# Low_MOS.net
KiCad netlist of a schematic drawn in Altium Designer
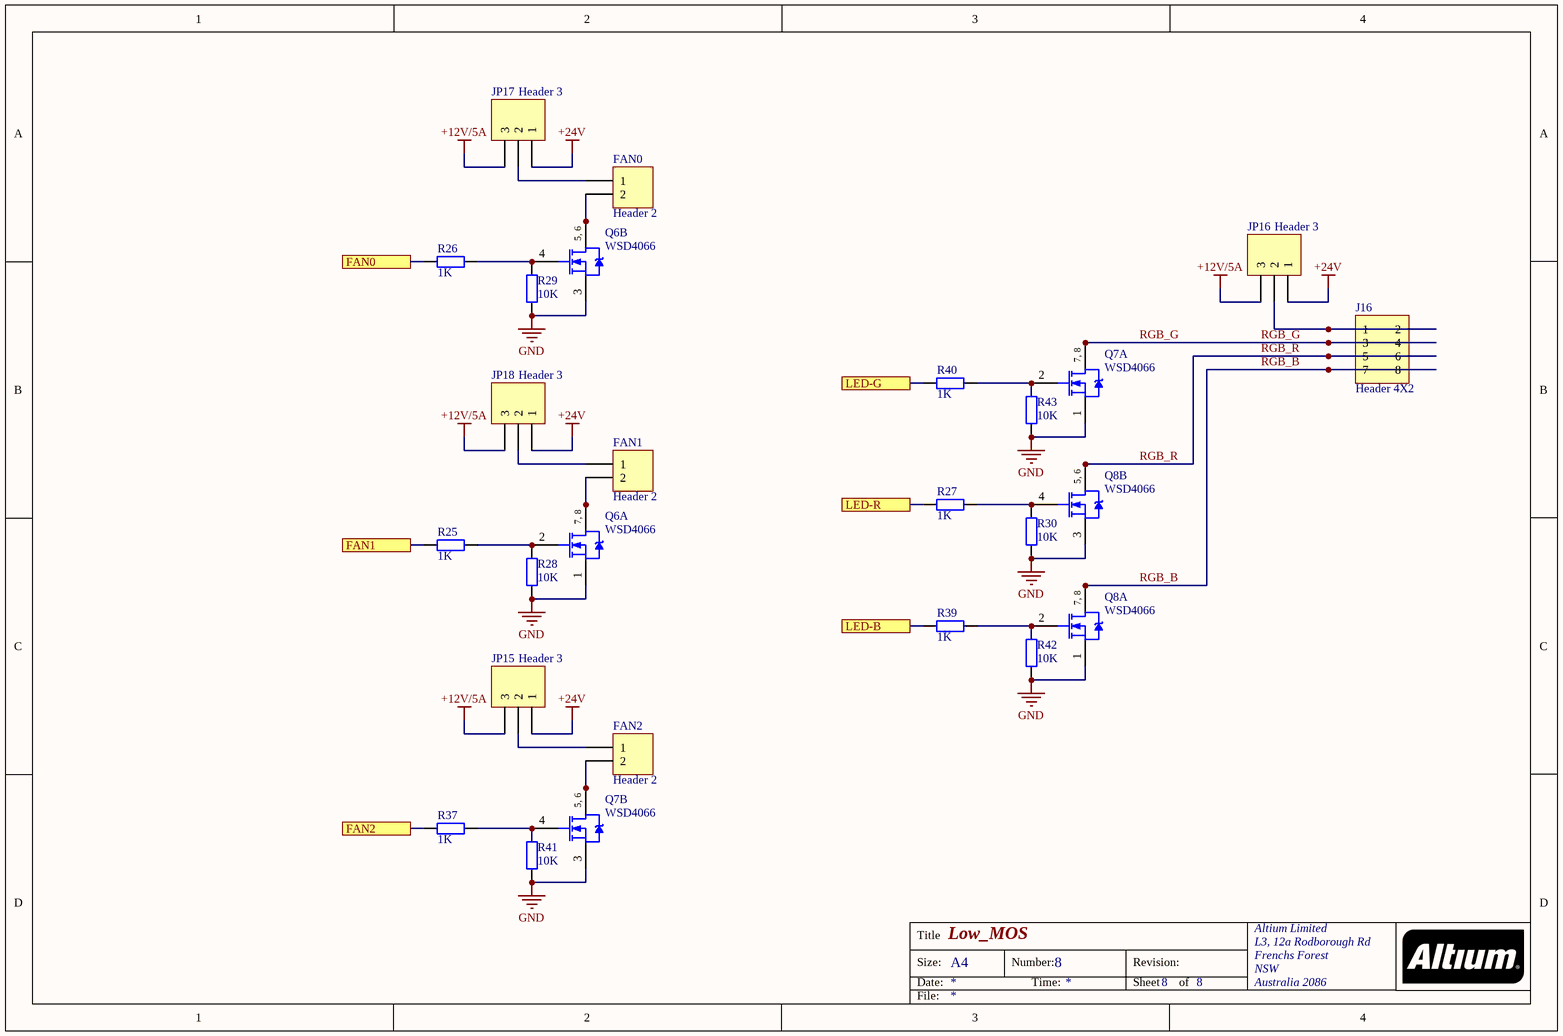
[diagram p0: Low_MOS.SchDoc]

(export (version "E")
  (design (tool "Eeschema 10.0.6"))
  (components
    (comp (ref "FAN0")
      (value "Header 2")
      (footprint "1X2 MTE STRAIGHT HEADER 2.54MM")
      (description "Header, 2-Pin")
      (fields (field (name "PUBLISHER") "Altium Limited"))
      (libsource (lib "Miscellaneous Connectors") (part "Header 2"))
    )
    (comp (ref "FAN1")
      (value "Header 2")
      (footprint "1X2 MTE STRAIGHT HEADER 2.54MM")
      (description "Header, 2-Pin")
      (fields (field (name "PUBLISHER") "Altium Limited"))
      (libsource (lib "Miscellaneous Connectors") (part "Header 2"))
    )
    (comp (ref "FAN2")
      (value "Header 2")
      (footprint "1X2 MTE STRAIGHT HEADER 2.54MM")
      (description "Header, 2-Pin")
      (fields (field (name "PUBLISHER") "Altium Limited"))
      (libsource (lib "Miscellaneous Connectors") (part "Header 2"))
    )
    (comp (ref "J16")
      (value "Header 4X2")
      (footprint "Header 2X4")
      (description "Header, 4-Pin, Dual row")
      (fields (field (name "PUBLISHER") "Altium Limited"))
      (libsource (lib "Miscellaneous Connectors") (part "Header 4X2"))
    )
    (comp (ref "JP15")
      (value "Header 3")
      (footprint "Header 1X3")
      (description "Header, 3-Pin")
      (fields (field (name "PUBLISHER") "Altium Limited"))
      (libsource (lib "Miscellaneous Connectors") (part "Header 3"))
    )
    (comp (ref "JP16")
      (value "Header 3")
      (footprint "Header 1X3")
      (description "Header, 3-Pin")
      (fields (field (name "PUBLISHER") "Altium Limited"))
      (libsource (lib "Miscellaneous Connectors") (part "Header 3"))
    )
    (comp (ref "JP17")
      (value "Header 3")
      (footprint "Header 1X3")
      (description "Header, 3-Pin")
      (fields (field (name "PUBLISHER") "Altium Limited"))
      (libsource (lib "Miscellaneous Connectors") (part "Header 3"))
    )
    (comp (ref "JP18")
      (value "Header 3")
      (footprint "Header 1X3")
      (description "Header, 3-Pin")
      (fields (field (name "PUBLISHER") "Altium Limited"))
      (libsource (lib "Miscellaneous Connectors") (part "Header 3"))
    )
    (comp (ref "Q6")
      (value "WSD4066")
      (footprint "DFN3X3-8L-Dual")
      (description "HEXFET Power MOSFET")
      (fields (field (name "PUBLISHER") "Altium Limited"))
      (libsource (lib "IR Discrete MOSFET - Power") (part "IRF7103"))
    )
    (comp (ref "Q7")
      (value "WSD4066")
      (footprint "DFN3X3-8L-Dual")
      (description "HEXFET Power MOSFET")
      (fields (field (name "PUBLISHER") "Altium Limited"))
      (libsource (lib "IR Discrete MOSFET - Power") (part "IRF7103"))
    )
    (comp (ref "Q8")
      (value "WSD4066")
      (footprint "DFN3X3-8L-Dual")
      (description "HEXFET Power MOSFET")
      (fields (field (name "PUBLISHER") "Altium Limited"))
      (libsource (lib "IR Discrete MOSFET - Power") (part "IRF7103"))
    )
    (comp (ref "R25") (value "1K") (footprint "RES0402") (libsource (lib "") (part "Resistor_1")))
    (comp (ref "R26") (value "1K") (footprint "RES0402") (libsource (lib "") (part "Resistor_1")))
    (comp (ref "R27") (value "1K") (footprint "RES0402") (libsource (lib "") (part "Resistor_1")))
    (comp (ref "R28") (value "10K") (footprint "RES0402") (libsource (lib "接插件库") (part "Resistor")))
    (comp (ref "R29") (value "10K") (footprint "RES0402") (libsource (lib "接插件库") (part "Resistor")))
    (comp (ref "R30") (value "10K") (footprint "RES0402") (libsource (lib "接插件库") (part "Resistor")))
    (comp (ref "R37") (value "1K") (footprint "RES0402") (libsource (lib "") (part "Resistor_1")))
    (comp (ref "R39") (value "1K") (footprint "RES0402") (libsource (lib "") (part "Resistor_1")))
    (comp (ref "R40") (value "1K") (footprint "RES0402") (libsource (lib "") (part "Resistor_1")))
    (comp (ref "R41") (value "10K") (footprint "RES0402") (libsource (lib "接插件库") (part "Resistor")))
    (comp (ref "R42") (value "10K") (footprint "RES0402") (libsource (lib "接插件库") (part "Resistor")))
    (comp (ref "R43") (value "10K") (footprint "RES0402") (libsource (lib "接插件库") (part "Resistor")))
  )
  (nets
    (net (code "1") (name "+12V{slash}5A") (class "Default")
      (node (ref "JP15") (pin "3") (pinfunction "3_3") (pintype "passive"))
      (node (ref "JP16") (pin "3") (pinfunction "3_3") (pintype "passive"))
      (node (ref "JP17") (pin "3") (pinfunction "3_3") (pintype "passive"))
      (node (ref "JP18") (pin "3") (pinfunction "3_3") (pintype "passive"))
    )
    (net (code "2") (name "+24V") (class "Default")
      (node (ref "JP15") (pin "1") (pinfunction "1_1") (pintype "passive"))
      (node (ref "JP16") (pin "1") (pinfunction "1_1") (pintype "passive"))
      (node (ref "JP17") (pin "1") (pinfunction "1_1") (pintype "passive"))
      (node (ref "JP18") (pin "1") (pinfunction "1_1") (pintype "passive"))
    )
    (net (code "3") (name "/FAN0") (class "Default")
      (node (ref "R26") (pin "1") (pinfunction "1_1") (pintype "passive"))
    )
    (net (code "4") (name "/FAN1") (class "Default")
      (node (ref "R25") (pin "1") (pinfunction "1_1") (pintype "passive"))
    )
    (net (code "5") (name "/FAN2") (class "Default")
      (node (ref "R37") (pin "1") (pinfunction "1_1") (pintype "passive"))
    )
    (net (code "6") (name "/LED-B") (class "Default")
      (node (ref "R39") (pin "1") (pinfunction "1_1") (pintype "passive"))
    )
    (net (code "7") (name "/LED-G") (class "Default")
      (node (ref "R40") (pin "1") (pinfunction "1_1") (pintype "passive"))
    )
    (net (code "8") (name "/LED-R") (class "Default")
      (node (ref "R27") (pin "1") (pinfunction "1_1") (pintype "passive"))
    )
    (net (code "9") (name "/RGB_B") (class "Default")
      (node (ref "J16") (pin "7") (pinfunction "7_7") (pintype "passive"))
      (node (ref "J16") (pin "8") (pinfunction "8_8") (pintype "passive"))
      (node (ref "Q8") (pin "7") (pinfunction "D_7") (pintype "passive"))
      (node (ref "Q8") (pin "8") (pinfunction "D_8") (pintype "passive"))
    )
    (net (code "10") (name "/RGB_G") (class "Default")
      (node (ref "J16") (pin "3") (pinfunction "3_3") (pintype "passive"))
      (node (ref "J16") (pin "4") (pinfunction "4_4") (pintype "passive"))
      (node (ref "Q7") (pin "7") (pinfunction "D_7") (pintype "passive"))
      (node (ref "Q7") (pin "8") (pinfunction "D_8") (pintype "passive"))
    )
    (net (code "11") (name "/RGB_R") (class "Default")
      (node (ref "J16") (pin "5") (pinfunction "5_5") (pintype "passive"))
      (node (ref "J16") (pin "6") (pinfunction "6_6") (pintype "passive"))
      (node (ref "Q8") (pin "5") (pinfunction "D_5") (pintype "passive"))
      (node (ref "Q8") (pin "6") (pinfunction "D_6") (pintype "passive"))
    )
    (net (code "12") (name "GND") (class "Default")
      (node (ref "Q6") (pin "1") (pinfunction "S_1") (pintype "passive"))
      (node (ref "Q6") (pin "3") (pinfunction "S_3") (pintype "passive"))
      (node (ref "Q7") (pin "1") (pinfunction "S_1") (pintype "passive"))
      (node (ref "Q7") (pin "3") (pinfunction "S_3") (pintype "passive"))
      (node (ref "Q8") (pin "1") (pinfunction "S_1") (pintype "passive"))
      (node (ref "Q8") (pin "3") (pinfunction "S_3") (pintype "passive"))
      (node (ref "R28") (pin "2") (pinfunction "2_2") (pintype "passive"))
      (node (ref "R29") (pin "2") (pinfunction "2_2") (pintype "passive"))
      (node (ref "R30") (pin "2") (pinfunction "2_2") (pintype "passive"))
      (node (ref "R41") (pin "2") (pinfunction "2_2") (pintype "passive"))
      (node (ref "R42") (pin "2") (pinfunction "2_2") (pintype "passive"))
      (node (ref "R43") (pin "2") (pinfunction "2_2") (pintype "passive"))
    )
    (net (code "13") (name "Net-(FAN0-Pad1)") (class "Default")
      (node (ref "FAN0") (pin "1") (pinfunction "1_1") (pintype "passive"))
      (node (ref "JP17") (pin "2") (pinfunction "2_2") (pintype "passive"))
    )
    (net (code "14") (name "Net-(FAN0-Pad2)") (class "Default")
      (node (ref "FAN0") (pin "2") (pinfunction "2_2") (pintype "passive"))
      (node (ref "Q6") (pin "5") (pinfunction "D_5") (pintype "passive"))
      (node (ref "Q6") (pin "6") (pinfunction "D_6") (pintype "passive"))
    )
    (net (code "15") (name "Net-(FAN1-Pad1)") (class "Default")
      (node (ref "FAN1") (pin "1") (pinfunction "1_1") (pintype "passive"))
      (node (ref "JP18") (pin "2") (pinfunction "2_2") (pintype "passive"))
    )
    (net (code "16") (name "Net-(FAN1-Pad2)") (class "Default")
      (node (ref "FAN1") (pin "2") (pinfunction "2_2") (pintype "passive"))
      (node (ref "Q6") (pin "7") (pinfunction "D_7") (pintype "passive"))
      (node (ref "Q6") (pin "8") (pinfunction "D_8") (pintype "passive"))
    )
    (net (code "17") (name "Net-(FAN2-Pad1)") (class "Default")
      (node (ref "FAN2") (pin "1") (pinfunction "1_1") (pintype "passive"))
      (node (ref "JP15") (pin "2") (pinfunction "2_2") (pintype "passive"))
    )
    (net (code "18") (name "Net-(FAN2-Pad2)") (class "Default")
      (node (ref "FAN2") (pin "2") (pinfunction "2_2") (pintype "passive"))
      (node (ref "Q7") (pin "5") (pinfunction "D_5") (pintype "passive"))
      (node (ref "Q7") (pin "6") (pinfunction "D_6") (pintype "passive"))
    )
    (net (code "19") (name "Net-(J16-Pad1)") (class "Default")
      (node (ref "J16") (pin "1") (pinfunction "1_1") (pintype "passive"))
      (node (ref "J16") (pin "2") (pinfunction "2_2") (pintype "passive"))
      (node (ref "JP16") (pin "2") (pinfunction "2_2") (pintype "passive"))
    )
    (net (code "20") (name "Net-(Q6A-G)") (class "Default")
      (node (ref "Q6") (pin "2") (pinfunction "G_2") (pintype "passive"))
      (node (ref "R25") (pin "2") (pinfunction "2_2") (pintype "passive"))
      (node (ref "R28") (pin "1") (pinfunction "1_1") (pintype "passive"))
    )
    (net (code "21") (name "Net-(Q6B-G)") (class "Default")
      (node (ref "Q6") (pin "4") (pinfunction "G_4") (pintype "passive"))
      (node (ref "R26") (pin "2") (pinfunction "2_2") (pintype "passive"))
      (node (ref "R29") (pin "1") (pinfunction "1_1") (pintype "passive"))
    )
    (net (code "22") (name "Net-(Q7A-G)") (class "Default")
      (node (ref "Q7") (pin "2") (pinfunction "G_2") (pintype "passive"))
      (node (ref "R40") (pin "2") (pinfunction "2_2") (pintype "passive"))
      (node (ref "R43") (pin "1") (pinfunction "1_1") (pintype "passive"))
    )
    (net (code "23") (name "Net-(Q7B-G)") (class "Default")
      (node (ref "Q7") (pin "4") (pinfunction "G_4") (pintype "passive"))
      (node (ref "R37") (pin "2") (pinfunction "2_2") (pintype "passive"))
      (node (ref "R41") (pin "1") (pinfunction "1_1") (pintype "passive"))
    )
    (net (code "24") (name "Net-(Q8A-G)") (class "Default")
      (node (ref "Q8") (pin "2") (pinfunction "G_2") (pintype "passive"))
      (node (ref "R39") (pin "2") (pinfunction "2_2") (pintype "passive"))
      (node (ref "R42") (pin "1") (pinfunction "1_1") (pintype "passive"))
    )
    (net (code "25") (name "Net-(Q8B-G)") (class "Default")
      (node (ref "Q8") (pin "4") (pinfunction "G_4") (pintype "passive"))
      (node (ref "R27") (pin "2") (pinfunction "2_2") (pintype "passive"))
      (node (ref "R30") (pin "1") (pinfunction "1_1") (pintype "passive"))
    )
  )
)
